# Sheet1.net
KiCad netlist of a schematic drawn in Altium Designer
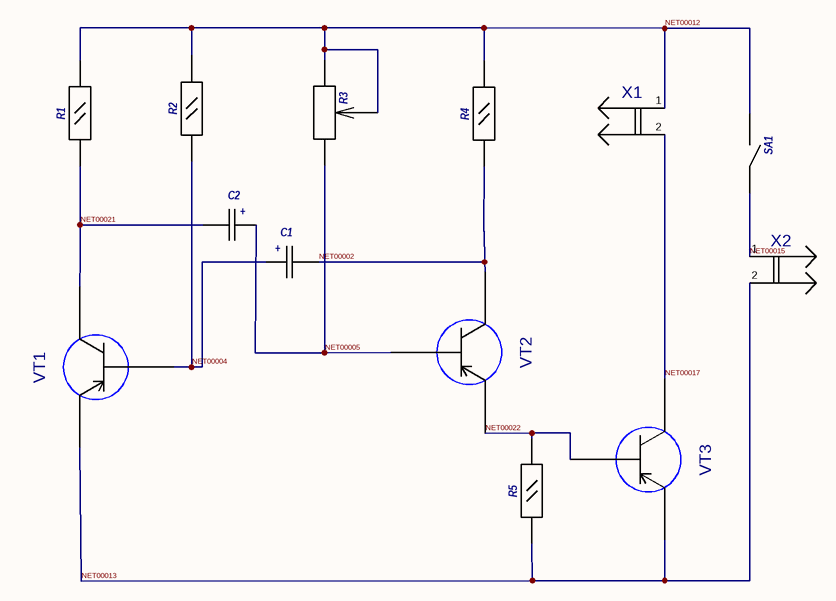
[diagram p0: Sheet1.SCHDOC]

(export (version "E")
  (design (tool "Eeschema 10.0.6"))
  (components
    (comp (ref "C1")
      (value "K50-29 (1;2,2;4,7;10;22 MK)")
      (footprint "К50-29 (17Х6)")
      (libsource (lib "*") (part "K50-29 (1;2,2;4,7;10;22 MK)"))
    )
    (comp (ref "C2")
      (value "K50-29 (1;2,2;4,7;10;22 MK)")
      (footprint "К50-29 (17Х6)")
      (libsource (lib "*") (part "K50-29 (1;2,2;4,7;10;22 MK)"))
    )
    (comp (ref "R1") (value "МЛТ(0.125)") (footprint "МЛТ(0.125)") (libsource (lib "*") (part "МЛТ(0.125)")))
    (comp (ref "R2") (value "МЛТ(0.125)") (footprint "МЛТ(0.125)") (libsource (lib "*") (part "МЛТ(0.125)")))
    (comp (ref "R3") (value "СП3-38В") (footprint "СП3-38В") (libsource (lib "*") (part "СП3-38В")))
    (comp (ref "R4") (value "МЛТ(0.125)") (footprint "МЛТ(0.125)") (libsource (lib "*") (part "МЛТ(0.125)")))
    (comp (ref "R5") (value "МЛТ(0.125)") (footprint "МЛТ(0.125)") (libsource (lib "") (part "МЛТ(0.125)_1")))
    (comp (ref "SA1") (value "T1") (footprint "Т1") (libsource (lib "*") (part "T1")))
    (comp (ref "VT1") (value "КТ837") (footprint "КТ837") (libsource (lib "") (part "КТ837_1")))
    (comp (ref "VT2") (value "КТ837") (footprint "КТ837") (libsource (lib "*") (part "КТ837")))
    (comp (ref "VT3") (value "КТ837") (footprint "КТ837") (libsource (lib "*") (part "КТ837")))
    (comp (ref "X1") (value "2XR") (footprint "2XR") (libsource (lib "") (part "2XR_1")))
    (comp (ref "X2") (value "2XR") (footprint "2XR") (libsource (lib "*") (part "2XR")))
  )
  (nets
    (net (code "1") (name "/NET00002") (class "Default")
      (node (ref "C1") (pin "1") (pinfunction "1_1") (pintype "passive"))
      (node (ref "R4") (pin "1") (pinfunction "1_1") (pintype "passive"))
      (node (ref "VT2") (pin "2") (pinfunction "A2_2") (pintype "passive"))
    )
    (net (code "2") (name "/NET00004") (class "Default")
      (node (ref "C1") (pin "2") (pinfunction "2_2") (pintype "passive"))
      (node (ref "R2") (pin "1") (pinfunction "1_1") (pintype "passive"))
      (node (ref "VT1") (pin "1") (pinfunction "A1_1") (pintype "passive"))
    )
    (net (code "3") (name "/NET00005") (class "Default")
      (node (ref "C2") (pin "2") (pinfunction "2_2") (pintype "passive"))
      (node (ref "R3") (pin "1") (pinfunction "1_1") (pintype "passive"))
      (node (ref "VT2") (pin "1") (pinfunction "A1_1") (pintype "passive"))
    )
    (net (code "4") (name "/NET00012") (class "Default")
      (node (ref "R1") (pin "2") (pinfunction "2_2") (pintype "passive"))
      (node (ref "R2") (pin "2") (pinfunction "2_2") (pintype "passive"))
      (node (ref "R3") (pin "2") (pinfunction "2_2") (pintype "passive"))
      (node (ref "R3") (pin "3") (pinfunction "3_3") (pintype "passive"))
      (node (ref "R4") (pin "2") (pinfunction "2_2") (pintype "passive"))
      (node (ref "SA1") (pin "2") (pinfunction "2_2") (pintype "passive"))
      (node (ref "X1") (pin "1") (pinfunction "I/O1_1") (pintype "passive"))
    )
    (net (code "5") (name "/NET00013") (class "Default")
      (node (ref "R5") (pin "1") (pinfunction "1_1") (pintype "passive"))
      (node (ref "VT1") (pin "3") (pinfunction "A3_3") (pintype "passive"))
      (node (ref "VT3") (pin "3") (pinfunction "A3_3") (pintype "passive"))
      (node (ref "X2") (pin "2") (pinfunction "I/O2_2") (pintype "passive"))
    )
    (net (code "6") (name "/NET00015") (class "Default")
      (node (ref "SA1") (pin "1") (pinfunction "1_1") (pintype "passive"))
      (node (ref "X2") (pin "1") (pinfunction "I/O1_1") (pintype "passive"))
    )
    (net (code "7") (name "/NET00017") (class "Default")
      (node (ref "VT3") (pin "2") (pinfunction "A2_2") (pintype "passive"))
      (node (ref "X1") (pin "2") (pinfunction "I/O2_2") (pintype "passive"))
    )
    (net (code "8") (name "/NET00021") (class "Default")
      (node (ref "C2") (pin "1") (pinfunction "1_1") (pintype "passive"))
      (node (ref "R1") (pin "1") (pinfunction "1_1") (pintype "passive"))
      (node (ref "VT1") (pin "2") (pinfunction "A2_2") (pintype "passive"))
    )
    (net (code "9") (name "/NET00022") (class "Default")
      (node (ref "R5") (pin "2") (pinfunction "2_2") (pintype "passive"))
      (node (ref "VT2") (pin "3") (pinfunction "A3_3") (pintype "passive"))
      (node (ref "VT3") (pin "1") (pinfunction "A1_1") (pintype "passive"))
    )
  )
)
